# GregsBoard1.net
KiCad netlist of a schematic drawn in EAGLE
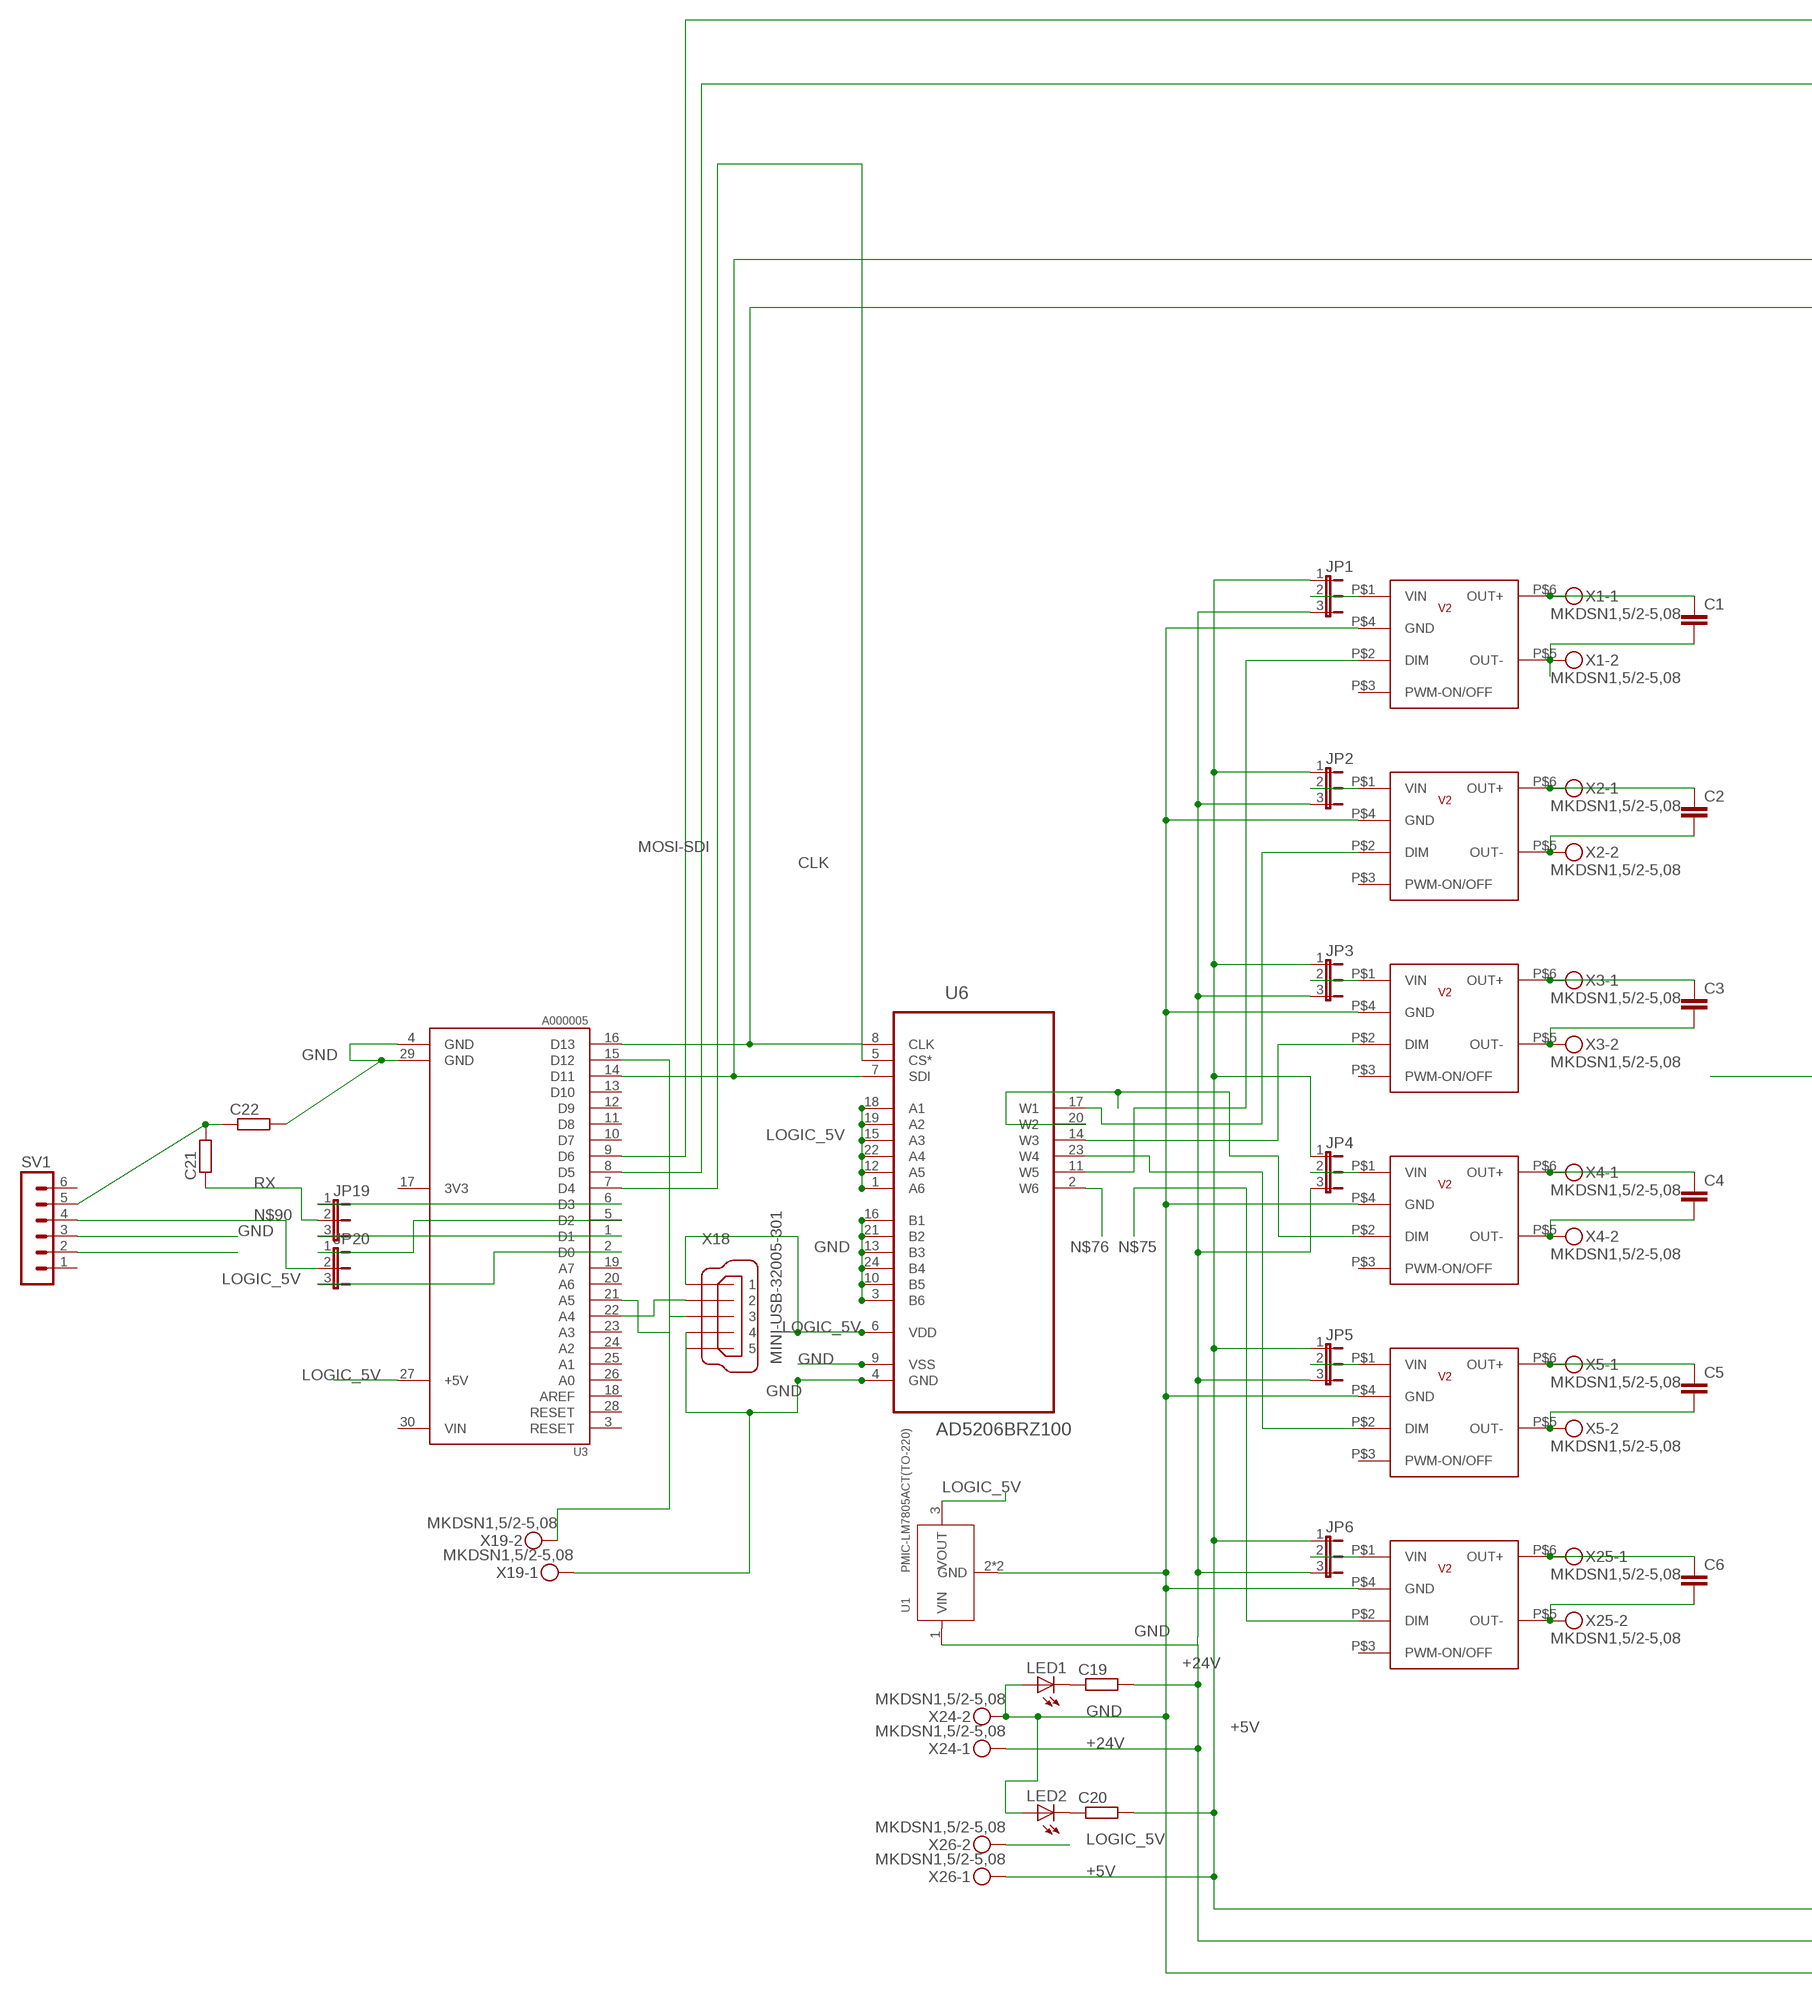
[diagram p0: schematic, sheet 1, part 1 of 2]
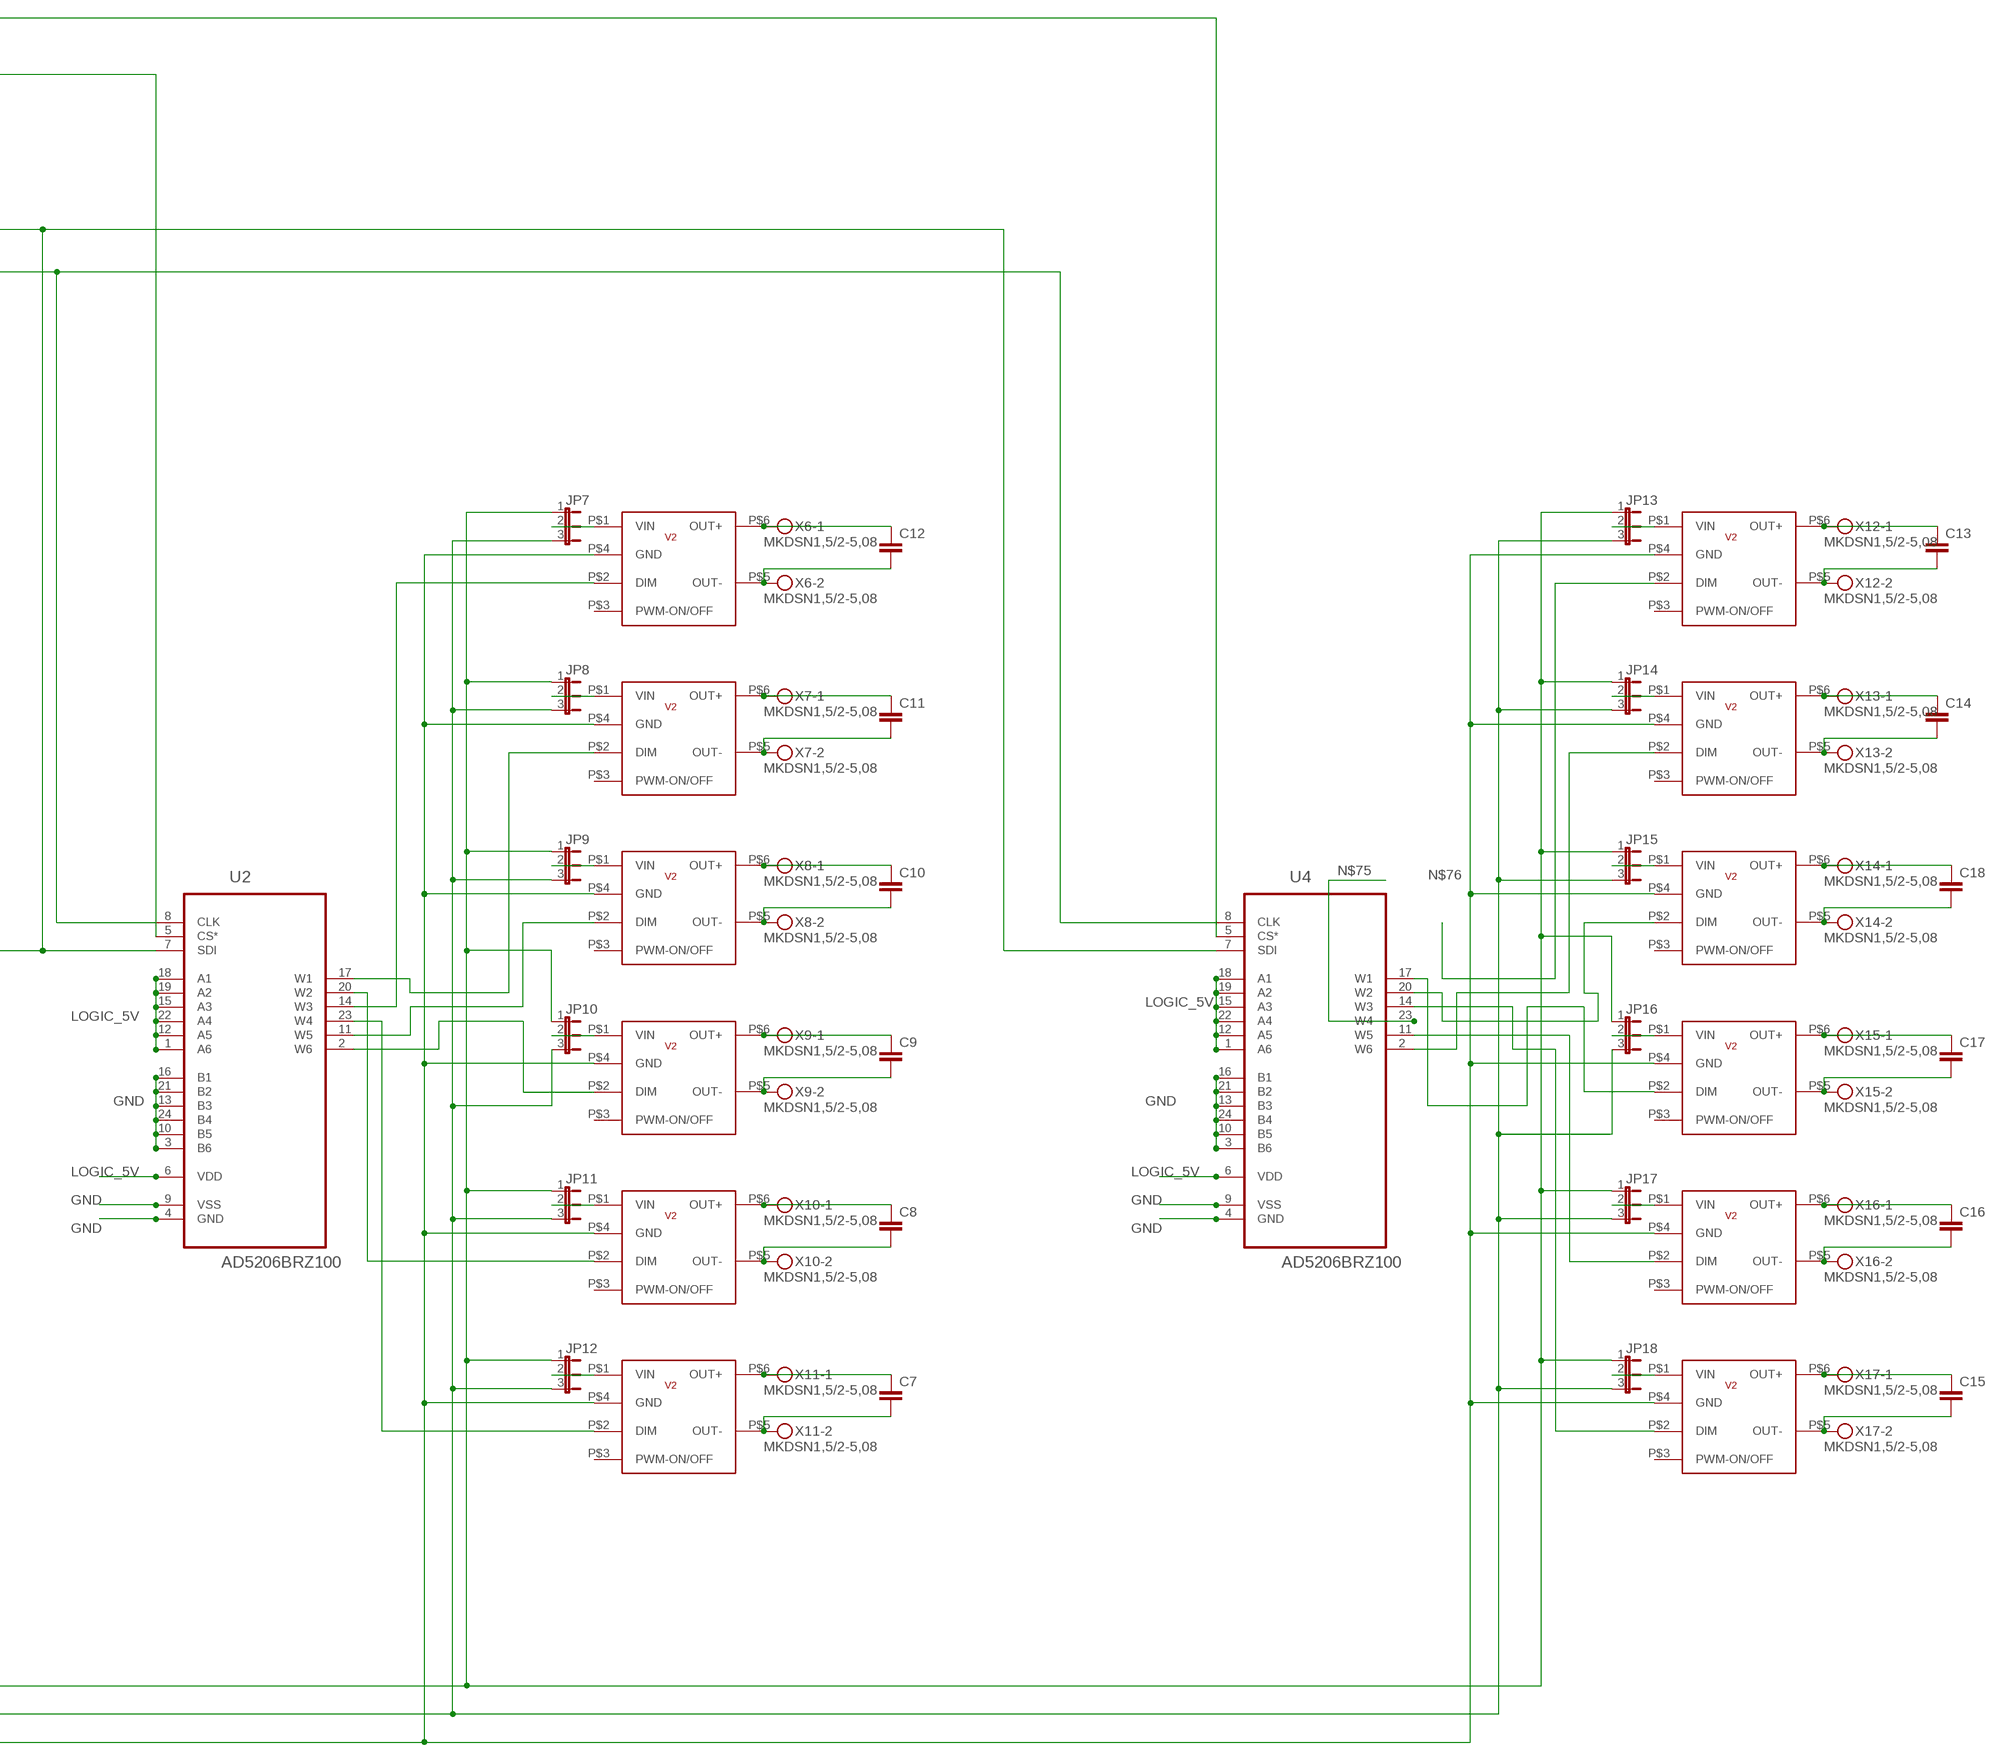
[diagram p1: schematic, sheet 1, part 2 of 2]

(export (version "E")
  (design (tool "Eeschema 10.0.6"))
  (components
    (comp (ref "C1")
      (value "C-EU050-045X075")
      (footprint "eagle-import:C050-045X075")
      (libsource (lib "eagle-import") (part "C-EU050-045X075"))
    )
    (comp (ref "C2")
      (value "C-EU050-045X075")
      (footprint "eagle-import:C050-045X075")
      (libsource (lib "eagle-import") (part "C-EU050-045X075"))
    )
    (comp (ref "C3")
      (value "C-EU050-045X075")
      (footprint "eagle-import:C050-045X075")
      (libsource (lib "eagle-import") (part "C-EU050-045X075"))
    )
    (comp (ref "C4")
      (value "C-EU050-045X075")
      (footprint "eagle-import:C050-045X075")
      (libsource (lib "eagle-import") (part "C-EU050-045X075"))
    )
    (comp (ref "C5")
      (value "C-EU050-045X075")
      (footprint "eagle-import:C050-045X075")
      (libsource (lib "eagle-import") (part "C-EU050-045X075"))
    )
    (comp (ref "C6")
      (value "C-EU050-045X075")
      (footprint "eagle-import:C050-045X075")
      (libsource (lib "eagle-import") (part "C-EU050-045X075"))
    )
    (comp (ref "C7")
      (value "C-EU050-045X075")
      (footprint "eagle-import:C050-045X075")
      (libsource (lib "eagle-import") (part "C-EU050-045X075"))
    )
    (comp (ref "C8")
      (value "C-EU050-045X075")
      (footprint "eagle-import:C050-045X075")
      (libsource (lib "eagle-import") (part "C-EU050-045X075"))
    )
    (comp (ref "C9")
      (value "C-EU050-045X075")
      (footprint "eagle-import:C050-045X075")
      (libsource (lib "eagle-import") (part "C-EU050-045X075"))
    )
    (comp (ref "C10")
      (value "C-EU050-045X075")
      (footprint "eagle-import:C050-045X075")
      (libsource (lib "eagle-import") (part "C-EU050-045X075"))
    )
    (comp (ref "C11")
      (value "C-EU050-045X075")
      (footprint "eagle-import:C050-045X075")
      (libsource (lib "eagle-import") (part "C-EU050-045X075"))
    )
    (comp (ref "C12")
      (value "C-EU050-045X075")
      (footprint "eagle-import:C050-045X075")
      (libsource (lib "eagle-import") (part "C-EU050-045X075"))
    )
    (comp (ref "C13")
      (value "C-EU050-045X075")
      (footprint "eagle-import:C050-045X075")
      (libsource (lib "eagle-import") (part "C-EU050-045X075"))
    )
    (comp (ref "C14")
      (value "C-EU050-045X075")
      (footprint "eagle-import:C050-045X075")
      (libsource (lib "eagle-import") (part "C-EU050-045X075"))
    )
    (comp (ref "C15")
      (value "C-EU050-045X075")
      (footprint "eagle-import:C050-045X075")
      (libsource (lib "eagle-import") (part "C-EU050-045X075"))
    )
    (comp (ref "C16")
      (value "C-EU050-045X075")
      (footprint "eagle-import:C050-045X075")
      (libsource (lib "eagle-import") (part "C-EU050-045X075"))
    )
    (comp (ref "C17")
      (value "C-EU050-045X075")
      (footprint "eagle-import:C050-045X075")
      (libsource (lib "eagle-import") (part "C-EU050-045X075"))
    )
    (comp (ref "C18")
      (value "C-EU050-045X075")
      (footprint "eagle-import:C050-045X075")
      (libsource (lib "eagle-import") (part "C-EU050-045X075"))
    )
    (comp (ref "C19")
      (value "R-EU_0207/7")
      (footprint "eagle-import:0207_7")
      (libsource (lib "eagle-import") (part "R-EU_0207/7"))
    )
    (comp (ref "C20")
      (value "R-EU_0207/7")
      (footprint "eagle-import:0207_7")
      (libsource (lib "eagle-import") (part "R-EU_0207/7"))
    )
    (comp (ref "C21")
      (value "R-EU_0207/7")
      (footprint "eagle-import:0207_7")
      (libsource (lib "eagle-import") (part "R-EU_0207/7"))
    )
    (comp (ref "C22")
      (value "R-EU_0207/7")
      (footprint "eagle-import:0207_7")
      (libsource (lib "eagle-import") (part "R-EU_0207/7"))
    )
    (comp (ref "IC1")
      (value "RCD-24_MY_DEV")
      (footprint "eagle-import:RCD24-DIP")
      (libsource (lib "eagle-import") (part "RCD-24_MY_DEV"))
    )
    (comp (ref "IC2")
      (value "RCD-24_MY_DEV")
      (footprint "eagle-import:RCD24-DIP")
      (libsource (lib "eagle-import") (part "RCD-24_MY_DEV"))
    )
    (comp (ref "IC3")
      (value "RCD-24_MY_DEV")
      (footprint "eagle-import:RCD24-DIP")
      (libsource (lib "eagle-import") (part "RCD-24_MY_DEV"))
    )
    (comp (ref "IC4")
      (value "RCD-24_MY_DEV")
      (footprint "eagle-import:RCD24-DIP")
      (libsource (lib "eagle-import") (part "RCD-24_MY_DEV"))
    )
    (comp (ref "IC5")
      (value "RCD-24_MY_DEV")
      (footprint "eagle-import:RCD24-DIP")
      (libsource (lib "eagle-import") (part "RCD-24_MY_DEV"))
    )
    (comp (ref "IC6")
      (value "RCD-24_MY_DEV")
      (footprint "eagle-import:RCD24-DIP")
      (libsource (lib "eagle-import") (part "RCD-24_MY_DEV"))
    )
    (comp (ref "IC7")
      (value "RCD-24_MY_DEV")
      (footprint "eagle-import:RCD24-DIP")
      (libsource (lib "eagle-import") (part "RCD-24_MY_DEV"))
    )
    (comp (ref "IC8")
      (value "RCD-24_MY_DEV")
      (footprint "eagle-import:RCD24-DIP")
      (libsource (lib "eagle-import") (part "RCD-24_MY_DEV"))
    )
    (comp (ref "IC9")
      (value "RCD-24_MY_DEV")
      (footprint "eagle-import:RCD24-DIP")
      (libsource (lib "eagle-import") (part "RCD-24_MY_DEV"))
    )
    (comp (ref "IC10")
      (value "RCD-24_MY_DEV")
      (footprint "eagle-import:RCD24-DIP")
      (libsource (lib "eagle-import") (part "RCD-24_MY_DEV"))
    )
    (comp (ref "IC11")
      (value "RCD-24_MY_DEV")
      (footprint "eagle-import:RCD24-DIP")
      (libsource (lib "eagle-import") (part "RCD-24_MY_DEV"))
    )
    (comp (ref "IC12")
      (value "RCD-24_MY_DEV")
      (footprint "eagle-import:RCD24-DIP")
      (libsource (lib "eagle-import") (part "RCD-24_MY_DEV"))
    )
    (comp (ref "IC13")
      (value "RCD-24_MY_DEV")
      (footprint "eagle-import:RCD24-DIP")
      (libsource (lib "eagle-import") (part "RCD-24_MY_DEV"))
    )
    (comp (ref "IC14")
      (value "RCD-24_MY_DEV")
      (footprint "eagle-import:RCD24-DIP")
      (libsource (lib "eagle-import") (part "RCD-24_MY_DEV"))
    )
    (comp (ref "IC15")
      (value "RCD-24_MY_DEV")
      (footprint "eagle-import:RCD24-DIP")
      (libsource (lib "eagle-import") (part "RCD-24_MY_DEV"))
    )
    (comp (ref "IC16")
      (value "RCD-24_MY_DEV")
      (footprint "eagle-import:RCD24-DIP")
      (libsource (lib "eagle-import") (part "RCD-24_MY_DEV"))
    )
    (comp (ref "IC17")
      (value "RCD-24_MY_DEV")
      (footprint "eagle-import:RCD24-DIP")
      (libsource (lib "eagle-import") (part "RCD-24_MY_DEV"))
    )
    (comp (ref "IC18")
      (value "RCD-24_MY_DEV")
      (footprint "eagle-import:RCD24-DIP")
      (libsource (lib "eagle-import") (part "RCD-24_MY_DEV"))
    )
    (comp (ref "JP1")
      (value "JP2E")
      (footprint "eagle-import:JP2")
      (libsource (lib "eagle-import") (part "JP2E"))
    )
    (comp (ref "JP2")
      (value "JP2E")
      (footprint "eagle-import:JP2")
      (libsource (lib "eagle-import") (part "JP2E"))
    )
    (comp (ref "JP3")
      (value "JP2E")
      (footprint "eagle-import:JP2")
      (libsource (lib "eagle-import") (part "JP2E"))
    )
    (comp (ref "JP4")
      (value "JP2E")
      (footprint "eagle-import:JP2")
      (libsource (lib "eagle-import") (part "JP2E"))
    )
    (comp (ref "JP5")
      (value "JP2E")
      (footprint "eagle-import:JP2")
      (libsource (lib "eagle-import") (part "JP2E"))
    )
    (comp (ref "JP6")
      (value "JP2E")
      (footprint "eagle-import:JP2")
      (libsource (lib "eagle-import") (part "JP2E"))
    )
    (comp (ref "JP7")
      (value "JP2E")
      (footprint "eagle-import:JP2")
      (libsource (lib "eagle-import") (part "JP2E"))
    )
    (comp (ref "JP8")
      (value "JP2E")
      (footprint "eagle-import:JP2")
      (libsource (lib "eagle-import") (part "JP2E"))
    )
    (comp (ref "JP9")
      (value "JP2E")
      (footprint "eagle-import:JP2")
      (libsource (lib "eagle-import") (part "JP2E"))
    )
    (comp (ref "JP10")
      (value "JP2E")
      (footprint "eagle-import:JP2")
      (libsource (lib "eagle-import") (part "JP2E"))
    )
    (comp (ref "JP11")
      (value "JP2E")
      (footprint "eagle-import:JP2")
      (libsource (lib "eagle-import") (part "JP2E"))
    )
    (comp (ref "JP12")
      (value "JP2E")
      (footprint "eagle-import:JP2")
      (libsource (lib "eagle-import") (part "JP2E"))
    )
    (comp (ref "JP13")
      (value "JP2E")
      (footprint "eagle-import:JP2")
      (libsource (lib "eagle-import") (part "JP2E"))
    )
    (comp (ref "JP14")
      (value "JP2E")
      (footprint "eagle-import:JP2")
      (libsource (lib "eagle-import") (part "JP2E"))
    )
    (comp (ref "JP15")
      (value "JP2E")
      (footprint "eagle-import:JP2")
      (libsource (lib "eagle-import") (part "JP2E"))
    )
    (comp (ref "JP16")
      (value "JP2E")
      (footprint "eagle-import:JP2")
      (libsource (lib "eagle-import") (part "JP2E"))
    )
    (comp (ref "JP17")
      (value "JP2E")
      (footprint "eagle-import:JP2")
      (libsource (lib "eagle-import") (part "JP2E"))
    )
    (comp (ref "JP18")
      (value "JP2E")
      (footprint "eagle-import:JP2")
      (libsource (lib "eagle-import") (part "JP2E"))
    )
    (comp (ref "JP19")
      (value "JP2E")
      (footprint "eagle-import:JP2")
      (libsource (lib "eagle-import") (part "JP2E"))
    )
    (comp (ref "JP20")
      (value "JP2E")
      (footprint "eagle-import:JP2")
      (libsource (lib "eagle-import") (part "JP2E"))
    )
    (comp (ref "LED1")
      (value "LEDB152")
      (footprint "eagle-import:Q62902-B152")
      (libsource (lib "eagle-import") (part "LEDB152"))
    )
    (comp (ref "LED2")
      (value "LEDB152")
      (footprint "eagle-import:Q62902-B152")
      (libsource (lib "eagle-import") (part "LEDB152"))
    )
    (comp (ref "SV1")
      (value "MA06-1")
      (footprint "eagle-import:MA06-1")
      (libsource (lib "eagle-import") (part "MA06-1"))
    )
    (comp (ref "U1")
      (value "PMIC-LM7805ACT(TO-220)")
      (footprint "eagle-import:TO-220")
      (fields (field (name "MF") "ON Semiconductor") (field (name "MP") "LM7805ACT"))
      (libsource (lib "eagle-import") (part "PMIC-LM7805ACT(TO-220)"))
    )
    (comp (ref "U2")
      (value "AD5206BRZ100")
      (footprint "eagle-import:SOIC127P1032X265-24N")
      (fields (field (name "MF") "Analog"))
      (libsource (lib "eagle-import") (part "AD5206BRZ100"))
    )
    (comp (ref "U3")
      (value "A000005")
      (footprint "eagle-import:ARDUINO_A000005")
      (fields (field (name "MF") "Arduino"))
      (libsource (lib "eagle-import") (part "A000005"))
    )
    (comp (ref "U4")
      (value "AD5206BRZ100")
      (footprint "eagle-import:SOIC127P1032X265-24N")
      (fields (field (name "MF") "Analog"))
      (libsource (lib "eagle-import") (part "AD5206BRZ100"))
    )
    (comp (ref "U6")
      (value "AD5206BRZ100")
      (footprint "eagle-import:SOIC127P1032X265-24N")
      (fields (field (name "MF") "Analog"))
      (libsource (lib "eagle-import") (part "AD5206BRZ100"))
    )
    (comp (ref "X1")
      (value "MKDSN1,5/2-5,08")
      (footprint "eagle-import:MKDSN1,5_2-5,08")
      (libsource (lib "eagle-import") (part "MKDSN1,5/2-5,08"))
    )
    (comp (ref "X2")
      (value "MKDSN1,5/2-5,08")
      (footprint "eagle-import:MKDSN1,5_2-5,08")
      (libsource (lib "eagle-import") (part "MKDSN1,5/2-5,08"))
    )
    (comp (ref "X3")
      (value "MKDSN1,5/2-5,08")
      (footprint "eagle-import:MKDSN1,5_2-5,08")
      (libsource (lib "eagle-import") (part "MKDSN1,5/2-5,08"))
    )
    (comp (ref "X4")
      (value "MKDSN1,5/2-5,08")
      (footprint "eagle-import:MKDSN1,5_2-5,08")
      (libsource (lib "eagle-import") (part "MKDSN1,5/2-5,08"))
    )
    (comp (ref "X5")
      (value "MKDSN1,5/2-5,08")
      (footprint "eagle-import:MKDSN1,5_2-5,08")
      (libsource (lib "eagle-import") (part "MKDSN1,5/2-5,08"))
    )
    (comp (ref "X6")
      (value "MKDSN1,5/2-5,08")
      (footprint "eagle-import:MKDSN1,5_2-5,08")
      (libsource (lib "eagle-import") (part "MKDSN1,5/2-5,08"))
    )
    (comp (ref "X7")
      (value "MKDSN1,5/2-5,08")
      (footprint "eagle-import:MKDSN1,5_2-5,08")
      (libsource (lib "eagle-import") (part "MKDSN1,5/2-5,08"))
    )
    (comp (ref "X8")
      (value "MKDSN1,5/2-5,08")
      (footprint "eagle-import:MKDSN1,5_2-5,08")
      (libsource (lib "eagle-import") (part "MKDSN1,5/2-5,08"))
    )
    (comp (ref "X9")
      (value "MKDSN1,5/2-5,08")
      (footprint "eagle-import:MKDSN1,5_2-5,08")
      (libsource (lib "eagle-import") (part "MKDSN1,5/2-5,08"))
    )
    (comp (ref "X10")
      (value "MKDSN1,5/2-5,08")
      (footprint "eagle-import:MKDSN1,5_2-5,08")
      (libsource (lib "eagle-import") (part "MKDSN1,5/2-5,08"))
    )
    (comp (ref "X11")
      (value "MKDSN1,5/2-5,08")
      (footprint "eagle-import:MKDSN1,5_2-5,08")
      (libsource (lib "eagle-import") (part "MKDSN1,5/2-5,08"))
    )
    (comp (ref "X12")
      (value "MKDSN1,5/2-5,08")
      (footprint "eagle-import:MKDSN1,5_2-5,08")
      (libsource (lib "eagle-import") (part "MKDSN1,5/2-5,08"))
    )
    (comp (ref "X13")
      (value "MKDSN1,5/2-5,08")
      (footprint "eagle-import:MKDSN1,5_2-5,08")
      (libsource (lib "eagle-import") (part "MKDSN1,5/2-5,08"))
    )
    (comp (ref "X14")
      (value "MKDSN1,5/2-5,08")
      (footprint "eagle-import:MKDSN1,5_2-5,08")
      (libsource (lib "eagle-import") (part "MKDSN1,5/2-5,08"))
    )
    (comp (ref "X15")
      (value "MKDSN1,5/2-5,08")
      (footprint "eagle-import:MKDSN1,5_2-5,08")
      (libsource (lib "eagle-import") (part "MKDSN1,5/2-5,08"))
    )
    (comp (ref "X16")
      (value "MKDSN1,5/2-5,08")
      (footprint "eagle-import:MKDSN1,5_2-5,08")
      (libsource (lib "eagle-import") (part "MKDSN1,5/2-5,08"))
    )
    (comp (ref "X17")
      (value "MKDSN1,5/2-5,08")
      (footprint "eagle-import:MKDSN1,5_2-5,08")
      (libsource (lib "eagle-import") (part "MKDSN1,5/2-5,08"))
    )
    (comp (ref "X18")
      (value "MINI-USB-32005-301")
      (footprint "eagle-import:32005-301")
      (libsource (lib "eagle-import") (part "MINI-USB-32005-301"))
    )
    (comp (ref "X19")
      (value "MKDSN1,5/2-5,08")
      (footprint "eagle-import:MKDSN1,5_2-5,08")
      (libsource (lib "eagle-import") (part "MKDSN1,5/2-5,08"))
    )
    (comp (ref "X24")
      (value "MKDSN1,5/2-5,08")
      (footprint "eagle-import:MKDSN1,5_2-5,08")
      (libsource (lib "eagle-import") (part "MKDSN1,5/2-5,08"))
    )
    (comp (ref "X25")
      (value "MKDSN1,5/2-5,08")
      (footprint "eagle-import:MKDSN1,5_2-5,08")
      (libsource (lib "eagle-import") (part "MKDSN1,5/2-5,08"))
    )
    (comp (ref "X26")
      (value "MKDSN1,5/2-5,08")
      (footprint "eagle-import:MKDSN1,5_2-5,08")
      (libsource (lib "eagle-import") (part "MKDSN1,5/2-5,08"))
    )
  )
  (nets
    (net (code "1") (name "/+5V") (class "Default")
      (node (ref "C20") (pin "2") (pinfunction "2_2") (pintype "passive"))
      (node (ref "JP1") (pin "1") (pinfunction "1_1") (pintype "passive"))
      (node (ref "JP10") (pin "1") (pinfunction "1_1") (pintype "passive"))
      (node (ref "JP11") (pin "1") (pinfunction "1_1") (pintype "passive"))
      (node (ref "JP12") (pin "1") (pinfunction "1_1") (pintype "passive"))
      (node (ref "JP13") (pin "1") (pinfunction "1_1") (pintype "passive"))
      (node (ref "JP14") (pin "1") (pinfunction "1_1") (pintype "passive"))
      (node (ref "JP15") (pin "1") (pinfunction "1_1") (pintype "passive"))
      (node (ref "JP16") (pin "1") (pinfunction "1_1") (pintype "passive"))
      (node (ref "JP17") (pin "1") (pinfunction "1_1") (pintype "passive"))
      (node (ref "JP18") (pin "1") (pinfunction "1_1") (pintype "passive"))
      (node (ref "JP2") (pin "1") (pinfunction "1_1") (pintype "passive"))
      (node (ref "JP3") (pin "1") (pinfunction "1_1") (pintype "passive"))
      (node (ref "JP4") (pin "1") (pinfunction "1_1") (pintype "passive"))
      (node (ref "JP5") (pin "1") (pinfunction "1_1") (pintype "passive"))
      (node (ref "JP6") (pin "1") (pinfunction "1_1") (pintype "passive"))
      (node (ref "JP7") (pin "1") (pinfunction "1_1") (pintype "passive"))
      (node (ref "JP8") (pin "1") (pinfunction "1_1") (pintype "passive"))
      (node (ref "JP9") (pin "1") (pinfunction "1_1") (pintype "passive"))
      (node (ref "X26") (pin "1") (pinfunction "KL_1") (pintype "passive"))
    )
    (net (code "2") (name "/+24V") (class "Default")
      (node (ref "C19") (pin "2") (pinfunction "2_2") (pintype "passive"))
      (node (ref "JP1") (pin "3") (pinfunction "3_3") (pintype "passive"))
      (node (ref "JP10") (pin "3") (pinfunction "3_3") (pintype "passive"))
      (node (ref "JP11") (pin "3") (pinfunction "3_3") (pintype "passive"))
      (node (ref "JP12") (pin "3") (pinfunction "3_3") (pintype "passive"))
      (node (ref "JP13") (pin "3") (pinfunction "3_3") (pintype "passive"))
      (node (ref "JP14") (pin "3") (pinfunction "3_3") (pintype "passive"))
      (node (ref "JP15") (pin "3") (pinfunction "3_3") (pintype "passive"))
      (node (ref "JP16") (pin "3") (pinfunction "3_3") (pintype "passive"))
      (node (ref "JP17") (pin "3") (pinfunction "3_3") (pintype "passive"))
      (node (ref "JP18") (pin "3") (pinfunction "3_3") (pintype "passive"))
      (node (ref "JP2") (pin "3") (pinfunction "3_3") (pintype "passive"))
      (node (ref "JP3") (pin "3") (pinfunction "3_3") (pintype "passive"))
      (node (ref "JP4") (pin "3") (pinfunction "3_3") (pintype "passive"))
      (node (ref "JP5") (pin "3") (pinfunction "3_3") (pintype "passive"))
      (node (ref "JP6") (pin "3") (pinfunction "3_3") (pintype "passive"))
      (node (ref "JP7") (pin "3") (pinfunction "3_3") (pintype "passive"))
      (node (ref "JP8") (pin "3") (pinfunction "3_3") (pintype "passive"))
      (node (ref "JP9") (pin "3") (pinfunction "3_3") (pintype "passive"))
      (node (ref "U1") (pin "1") (pinfunction "VIN_1") (pintype "bidirectional"))
      (node (ref "X24") (pin "1") (pinfunction "KL_1") (pintype "passive"))
    )
    (net (code "3") (name "/CLK") (class "Default")
      (node (ref "U2") (pin "8") (pinfunction "CLK_8") (pintype "passive"))
      (node (ref "U3") (pin "16") (pinfunction "D13_16") (pintype "bidirectional"))
      (node (ref "U4") (pin "8") (pinfunction "CLK_8") (pintype "passive"))
      (node (ref "U6") (pin "8") (pinfunction "CLK_8") (pintype "passive"))
    )
    (net (code "4") (name "/GND") (class "Default")
      (node (ref "C22") (pin "2") (pinfunction "2_2") (pintype "passive"))
      (node (ref "IC1") (pin "P$4") (pinfunction "GND_P$4") (pintype "bidirectional"))
      (node (ref "IC10") (pin "P$4") (pinfunction "GND_P$4") (pintype "bidirectional"))
      (node (ref "IC11") (pin "P$4") (pinfunction "GND_P$4") (pintype "bidirectional"))
      (node (ref "IC12") (pin "P$4") (pinfunction "GND_P$4") (pintype "bidirectional"))
      (node (ref "IC13") (pin "P$4") (pinfunction "GND_P$4") (pintype "bidirectional"))
      (node (ref "IC14") (pin "P$4") (pinfunction "GND_P$4") (pintype "bidirectional"))
      (node (ref "IC15") (pin "P$4") (pinfunction "GND_P$4") (pintype "bidirectional"))
      (node (ref "IC16") (pin "P$4") (pinfunction "GND_P$4") (pintype "bidirectional"))
      (node (ref "IC17") (pin "P$4") (pinfunction "GND_P$4") (pintype "bidirectional"))
      (node (ref "IC18") (pin "P$4") (pinfunction "GND_P$4") (pintype "bidirectional"))
      (node (ref "IC2") (pin "P$4") (pinfunction "GND_P$4") (pintype "bidirectional"))
      (node (ref "IC3") (pin "P$4") (pinfunction "GND_P$4") (pintype "bidirectional"))
      (node (ref "IC4") (pin "P$4") (pinfunction "GND_P$4") (pintype "bidirectional"))
      (node (ref "IC5") (pin "P$4") (pinfunction "GND_P$4") (pintype "bidirectional"))
      (node (ref "IC6") (pin "P$4") (pinfunction "GND_P$4") (pintype "bidirectional"))
      (node (ref "IC7") (pin "P$4") (pinfunction "GND_P$4") (pintype "bidirectional"))
      (node (ref "IC8") (pin "P$4") (pinfunction "GND_P$4") (pintype "bidirectional"))
      (node (ref "IC9") (pin "P$4") (pinfunction "GND_P$4") (pintype "bidirectional"))
      (node (ref "LED1") (pin "A") (pinfunction "A_A") (pintype "passive"))
      (node (ref "LED2") (pin "A") (pinfunction "A_A") (pintype "passive"))
      (node (ref "SV1") (pin "3") (pinfunction "3_3") (pintype "passive"))
      (node (ref "U1") (pin "2") (pinfunction "GND_2") (pintype "bidirectional"))
      (node (ref "U1") (pin "HEAT") (pinfunction "GND_HEAT") (pintype "bidirectional"))
      (node (ref "U2") (pin "10") (pinfunction "B5_10") (pintype "passive"))
      (node (ref "U2") (pin "13") (pinfunction "B3_13") (pintype "passive"))
      (node (ref "U2") (pin "16") (pinfunction "B1_16") (pintype "passive"))
      (node (ref "U2") (pin "21") (pinfunction "B2_21") (pintype "passive"))
      (node (ref "U2") (pin "24") (pinfunction "B4_24") (pintype "passive"))
      (node (ref "U2") (pin "3") (pinfunction "B6_3") (pintype "passive"))
      (node (ref "U2") (pin "4") (pinfunction "GND_4") (pintype "passive"))
      (node (ref "U2") (pin "9") (pinfunction "VSS_9") (pintype "power_in"))
      (node (ref "U3") (pin "29") (pinfunction "GND_29") (pintype "power_in"))
      (node (ref "U3") (pin "4") (pinfunction "GND_4") (pintype "power_in"))
      (node (ref "U4") (pin "10") (pinfunction "B5_10") (pintype "passive"))
      (node (ref "U4") (pin "13") (pinfunction "B3_13") (pintype "passive"))
      (node (ref "U4") (pin "16") (pinfunction "B1_16") (pintype "passive"))
      (node (ref "U4") (pin "21") (pinfunction "B2_21") (pintype "passive"))
      (node (ref "U4") (pin "24") (pinfunction "B4_24") (pintype "passive"))
      (node (ref "U4") (pin "3") (pinfunction "B6_3") (pintype "passive"))
      (node (ref "U4") (pin "4") (pinfunction "GND_4") (pintype "passive"))
      (node (ref "U4") (pin "9") (pinfunction "VSS_9") (pintype "power_in"))
      (node (ref "U6") (pin "10") (pinfunction "B5_10") (pintype "passive"))
      (node (ref "U6") (pin "13") (pinfunction "B3_13") (pintype "passive"))
      (node (ref "U6") (pin "16") (pinfunction "B1_16") (pintype "passive"))
      (node (ref "U6") (pin "21") (pinfunction "B2_21") (pintype "passive"))
      (node (ref "U6") (pin "24") (pinfunction "B4_24") (pintype "passive"))
      (node (ref "U6") (pin "3") (pinfunction "B6_3") (pintype "passive"))
      (node (ref "U6") (pin "4") (pinfunction "GND_4") (pintype "passive"))
      (node (ref "U6") (pin "9") (pinfunction "VSS_9") (pintype "power_in"))
      (node (ref "X18") (pin "4") (pinfunction "4_4") (pintype "passive"))
      (node (ref "X19") (pin "1") (pinfunction "KL_1") (pintype "passive"))
      (node (ref "X24") (pin "2") (pinfunction "KL_2") (pintype "passive"))
    )
    (net (code "5") (name "/LOGIC_5V") (class "Default")
      (node (ref "SV1") (pin "2") (pinfunction "2_2") (pintype "passive"))
      (node (ref "U1") (pin "3") (pinfunction "VOUT_3") (pintype "bidirectional"))
      (node (ref "U2") (pin "1") (pinfunction "A6_1") (pintype "passive"))
      (node (ref "U2") (pin "12") (pinfunction "A5_12") (pintype "passive"))
      (node (ref "U2") (pin "15") (pinfunction "A3_15") (pintype "passive"))
      (node (ref "U2") (pin "18") (pinfunction "A1_18") (pintype "passive"))
      (node (ref "U2") (pin "19") (pinfunction "A2_19") (pintype "passive"))
      (node (ref "U2") (pin "22") (pinfunction "A4_22") (pintype "passive"))
      (node (ref "U2") (pin "6") (pinfunction "VDD_6") (pintype "power_in"))
      (node (ref "U3") (pin "27") (pinfunction "+5V_27") (pintype "power_in"))
      (node (ref "U4") (pin "1") (pinfunction "A6_1") (pintype "passive"))
      (node (ref "U4") (pin "12") (pinfunction "A5_12") (pintype "passive"))
      (node (ref "U4") (pin "15") (pinfunction "A3_15") (pintype "passive"))
      (node (ref "U4") (pin "18") (pinfunction "A1_18") (pintype "passive"))
      (node (ref "U4") (pin "19") (pinfunction "A2_19") (pintype "passive"))
      (node (ref "U4") (pin "22") (pinfunction "A4_22") (pintype "passive"))
      (node (ref "U4") (pin "6") (pinfunction "VDD_6") (pintype "power_in"))
      (node (ref "U6") (pin "1") (pinfunction "A6_1") (pintype "passive"))
      (node (ref "U6") (pin "12") (pinfunction "A5_12") (pintype "passive"))
      (node (ref "U6") (pin "15") (pinfunction "A3_15") (pintype "passive"))
      (node (ref "U6") (pin "18") (pinfunction "A1_18") (pintype "passive"))
      (node (ref "U6") (pin "19") (pinfunction "A2_19") (pintype "passive"))
      (node (ref "U6") (pin "22") (pinfunction "A4_22") (pintype "passive"))
      (node (ref "U6") (pin "6") (pinfunction "VDD_6") (pintype "power_in"))
      (node (ref "X18") (pin "1") (pinfunction "1_1") (pintype "passive"))
      (node (ref "X26") (pin "2") (pinfunction "KL_2") (pintype "passive"))
    )
    (net (code "6") (name "/MOSI-SDI") (class "Default")
      (node (ref "U2") (pin "7") (pinfunction "SDI_7") (pintype "passive"))
      (node (ref "U3") (pin "14") (pinfunction "D11_14") (pintype "bidirectional"))
      (node (ref "U4") (pin "7") (pinfunction "SDI_7") (pintype "passive"))
      (node (ref "U6") (pin "7") (pinfunction "SDI_7") (pintype "passive"))
    )
    (net (code "7") (name "/N$75") (class "Default")
      (node (ref "IC1") (pin "P$2") (pinfunction "DIM_P$2") (pintype "bidirectional"))
      (node (ref "U4") (pin "23") (pinfunction "W4_23") (pintype "passive"))
    )
    (net (code "8") (name "/N$76") (class "Default")
      (node (ref "IC13") (pin "P$2") (pinfunction "DIM_P$2") (pintype "bidirectional"))
      (node (ref "U6") (pin "2") (pinfunction "W6_2") (pintype "passive"))
    )
    (net (code "9") (name "/N$90") (class "Default")
      (node (ref "JP20") (pin "2") (pinfunction "2_2") (pintype "passive"))
      (node (ref "SV1") (pin "4") (pinfunction "4_4") (pintype "passive"))
    )
    (net (code "10") (name "/RX") (class "Default")
      (node (ref "C21") (pin "2") (pinfunction "2_2") (pintype "passive"))
      (node (ref "C22") (pin "1") (pinfunction "1_1") (pintype "passive"))
      (node (ref "SV1") (pin "5") (pinfunction "5_5") (pintype "passive"))
    )
    (net (code "11") (name "/VIN") (class "Default")
      (node (ref "U3") (pin "30") (pinfunction "VIN_30") (pintype "power_in"))
    )
    (net (code "12") (name "Net-(C21-Pad1)") (class "Default")
      (node (ref "C21") (pin "1") (pinfunction "1_1") (pintype "passive"))
      (node (ref "JP19") (pin "2") (pinfunction "2_2") (pintype "passive"))
    )
    (net (code "13") (name "Net-(IC1-OUT+)") (class "Default")
      (node (ref "C6") (pin "1") (pinfunction "1_1") (pintype "passive"))
      (node (ref "IC1") (pin "P$6") (pinfunction "OUT+_P$6") (pintype "bidirectional"))
      (node (ref "X25") (pin "1") (pinfunction "KL_1") (pintype "passive"))
    )
    (net (code "14") (name "Net-(IC1-OUT-)") (class "Default")
      (node (ref "C6") (pin "2") (pinfunction "2_2") (pintype "passive"))
      (node (ref "IC1") (pin "P$5") (pinfunction "OUT-_P$5") (pintype "bidirectional"))
      (node (ref "X25") (pin "2") (pinfunction "KL_2") (pintype "passive"))
    )
    (net (code "15") (name "Net-(IC1-VIN)") (class "Default")
      (node (ref "IC1") (pin "P$1") (pinfunction "VIN_P$1") (pintype "bidirectional"))
      (node (ref "JP6") (pin "2") (pinfunction "2_2") (pintype "passive"))
    )
    (net (code "16") (name "Net-(IC2-DIM)") (class "Default")
      (node (ref "IC2") (pin "P$2") (pinfunction "DIM_P$2") (pintype "bidirectional"))
      (node (ref "U6") (pin "11") (pinfunction "W5_11") (pintype "passive"))
    )
    (net (code "17") (name "Net-(IC2-OUT+)") (class "Default")
      (node (ref "C1") (pin "1") (pinfunction "1_1") (pintype "passive"))
      (node (ref "IC2") (pin "P$6") (pinfunction "OUT+_P$6") (pintype "bidirectional"))
      (node (ref "X1") (pin "1") (pinfunction "KL_1") (pintype "passive"))
    )
    (net (code "18") (name "Net-(IC2-OUT-)") (class "Default")
      (node (ref "C1") (pin "2") (pinfunction "2_2") (pintype "passive"))
      (node (ref "IC2") (pin "P$5") (pinfunction "OUT-_P$5") (pintype "bidirectional"))
      (node (ref "X1") (pin "2") (pinfunction "KL_2") (pintype "passive"))
    )
    (net (code "19") (name "Net-(IC2-VIN)") (class "Default")
      (node (ref "IC2") (pin "P$1") (pinfunction "VIN_P$1") (pintype "bidirectional"))
      (node (ref "JP1") (pin "2") (pinfunction "2_2") (pintype "passive"))
    )
    (net (code "20") (name "Net-(IC3-DIM)") (class "Default")
      (node (ref "IC3") (pin "P$2") (pinfunction "DIM_P$2") (pintype "bidirectional"))
      (node (ref "U6") (pin "17") (pinfunction "W1_17") (pintype "passive"))
    )
    (net (code "21") (name "Net-(IC3-OUT+)") (class "Default")
      (node (ref "C2") (pin "1") (pinfunction "1_1") (pintype "passive"))
      (node (ref "IC3") (pin "P$6") (pinfunction "OUT+_P$6") (pintype "bidirectional"))
      (node (ref "X2") (pin "1") (pinfunction "KL_1") (pintype "passive"))
    )
    (net (code "22") (name "Net-(IC3-OUT-)") (class "Default")
      (node (ref "C2") (pin "2") (pinfunction "2_2") (pintype "passive"))
      (node (ref "IC3") (pin "P$5") (pinfunction "OUT-_P$5") (pintype "bidirectional"))
      (node (ref "X2") (pin "2") (pinfunction "KL_2") (pintype "passive"))
    )
    (net (code "23") (name "Net-(IC3-VIN)") (class "Default")
      (node (ref "IC3") (pin "P$1") (pinfunction "VIN_P$1") (pintype "bidirectional"))
      (node (ref "JP2") (pin "2") (pinfunction "2_2") (pintype "passive"))
    )
    (net (code "24") (name "Net-(IC4-DIM)") (class "Default")
      (node (ref "IC4") (pin "P$2") (pinfunction "DIM_P$2") (pintype "bidirectional"))
      (node (ref "U6") (pin "14") (pinfunction "W3_14") (pintype "passive"))
    )
    (net (code "25") (name "Net-(IC4-OUT+)") (class "Default")
      (node (ref "C3") (pin "1") (pinfunction "1_1") (pintype "passive"))
      (node (ref "IC4") (pin "P$6") (pinfunction "OUT+_P$6") (pintype "bidirectional"))
      (node (ref "X3") (pin "1") (pinfunction "KL_1") (pintype "passive"))
    )
    (net (code "26") (name "Net-(IC4-OUT-)") (class "Default")
      (node (ref "C3") (pin "2") (pinfunction "2_2") (pintype "passive"))
      (node (ref "IC4") (pin "P$5") (pinfunction "OUT-_P$5") (pintype "bidirectional"))
      (node (ref "X3") (pin "2") (pinfunction "KL_2") (pintype "passive"))
    )
    (net (code "27") (name "Net-(IC4-VIN)") (class "Default")
      (node (ref "IC4") (pin "P$1") (pinfunction "VIN_P$1") (pintype "bidirectional"))
      (node (ref "JP3") (pin "2") (pinfunction "2_2") (pintype "passive"))
    )
    (net (code "28") (name "Net-(IC5-DIM)") (class "Default")
      (node (ref "IC5") (pin "P$2") (pinfunction "DIM_P$2") (pintype "bidirectional"))
      (node (ref "U6") (pin "20") (pinfunction "W2_20") (pintype "passive"))
    )
    (net (code "29") (name "Net-(IC5-OUT+)") (class "Default")
      (node (ref "C4") (pin "1") (pinfunction "1_1") (pintype "passive"))
      (node (ref "IC5") (pin "P$6") (pinfunction "OUT+_P$6") (pintype "bidirectional"))
      (node (ref "X4") (pin "1") (pinfunction "KL_1") (pintype "passive"))
    )
    (net (code "30") (name "Net-(IC5-OUT-)") (class "Default")
      (node (ref "C4") (pin "2") (pinfunction "2_2") (pintype "passive"))
      (node (ref "IC5") (pin "P$5") (pinfunction "OUT-_P$5") (pintype "bidirectional"))
      (node (ref "X4") (pin "2") (pinfunction "KL_2") (pintype "passive"))
    )
    (net (code "31") (name "Net-(IC5-VIN)") (class "Default")
      (node (ref "IC5") (pin "P$1") (pinfunction "VIN_P$1") (pintype "bidirectional"))
      (node (ref "JP4") (pin "2") (pinfunction "2_2") (pintype "passive"))
    )
    (net (code "32") (name "Net-(IC6-DIM)") (class "Default")
      (node (ref "IC6") (pin "P$2") (pinfunction "DIM_P$2") (pintype "bidirectional"))
      (node (ref "U6") (pin "23") (pinfunction "W4_23") (pintype "passive"))
    )
    (net (code "33") (name "Net-(IC6-OUT+)") (class "Default")
      (node (ref "C5") (pin "1") (pinfunction "1_1") (pintype "passive"))
      (node (ref "IC6") (pin "P$6") (pinfunction "OUT+_P$6") (pintype "bidirectional"))
      (node (ref "X5") (pin "1") (pinfunction "KL_1") (pintype "passive"))
    )
    (net (code "34") (name "Net-(IC6-OUT-)") (class "Default")
      (node (ref "C5") (pin "2") (pinfunction "2_2") (pintype "passive"))
      (node (ref "IC6") (pin "P$5") (pinfunction "OUT-_P$5") (pintype "bidirectional"))
      (node (ref "X5") (pin "2") (pinfunction "KL_2") (pintype "passive"))
    )
    (net (code "35") (name "Net-(IC6-VIN)") (class "Default")
      (node (ref "IC6") (pin "P$1") (pinfunction "VIN_P$1") (pintype "bidirectional"))
      (node (ref "JP5") (pin "2") (pinfunction "2_2") (pintype "passive"))
    )
    (net (code "36") (name "Net-(IC7-DIM)") (class "Default")
      (node (ref "IC7") (pin "P$2") (pinfunction "DIM_P$2") (pintype "bidirectional"))
      (node (ref "U2") (pin "14") (pinfunction "W3_14") (pintype "passive"))
    )
    (net (code "37") (name "Net-(IC7-OUT+)") (class "Default")
      (node (ref "C12") (pin "1") (pinfunction "1_1") (pintype "passive"))
      (node (ref "IC7") (pin "P$6") (pinfunction "OUT+_P$6") (pintype "bidirectional"))
      (node (ref "X6") (pin "1") (pinfunction "KL_1") (pintype "passive"))
    )
    (net (code "38") (name "Net-(IC7-OUT-)") (class "Default")
      (node (ref "C12") (pin "2") (pinfunction "2_2") (pintype "passive"))
      (node (ref "IC7") (pin "P$5") (pinfunction "OUT-_P$5") (pintype "bidirectional"))
      (node (ref "X6") (pin "2") (pinfunction "KL_2") (pintype "passive"))
    )
    (net (code "39") (name "Net-(IC7-VIN)") (class "Default")
      (node (ref "IC7") (pin "P$1") (pinfunction "VIN_P$1") (pintype "bidirectional"))
      (node (ref "JP7") (pin "2") (pinfunction "2_2") (pintype "passive"))
    )
    (net (code "40") (name "Net-(IC8-DIM)") (class "Default")
      (node (ref "IC8") (pin "P$2") (pinfunction "DIM_P$2") (pintype "bidirectional"))
      (node (ref "U2") (pin "17") (pinfunction "W1_17") (pintype "passive"))
    )
    (net (code "41") (name "Net-(IC8-OUT+)") (class "Default")
      (node (ref "C11") (pin "1") (pinfunction "1_1") (pintype "passive"))
      (node (ref "IC8") (pin "P$6") (pinfunction "OUT+_P$6") (pintype "bidirectional"))
      (node (ref "X7") (pin "1") (pinfunction "KL_1") (pintype "passive"))
    )
    (net (code "42") (name "Net-(IC8-OUT-)") (class "Default")
      (node (ref "C11") (pin "2") (pinfunction "2_2") (pintype "passive"))
      (node (ref "IC8") (pin "P$5") (pinfunction "OUT-_P$5") (pintype "bidirectional"))
      (node (ref "X7") (pin "2") (pinfunction "KL_2") (pintype "passive"))
    )
    (net (code "43") (name "Net-(IC8-VIN)") (class "Default")
      (node (ref "IC8") (pin "P$1") (pinfunction "VIN_P$1") (pintype "bidirectional"))
      (node (ref "JP8") (pin "2") (pinfunction "2_2") (pintype "passive"))
    )
    (net (code "44") (name "Net-(IC9-DIM)") (class "Default")
      (node (ref "IC9") (pin "P$2") (pinfunction "DIM_P$2") (pintype "bidirectional"))
      (node (ref "U2") (pin "11") (pinfunction "W5_11") (pintype "passive"))
    )
    (net (code "45") (name "Net-(IC9-OUT+)") (class "Default")
      (node (ref "C10") (pin "1") (pinfunction "1_1") (pintype "passive"))
      (node (ref "IC9") (pin "P$6") (pinfunction "OUT+_P$6") (pintype "bidirectional"))
      (node (ref "X8") (pin "1") (pinfunction "KL_1") (pintype "passive"))
    )
    (net (code "46") (name "Net-(IC9-OUT-)") (class "Default")
      (node (ref "C10") (pin "2") (pinfunction "2_2") (pintype "passive"))
      (node (ref "IC9") (pin "P$5") (pinfunction "OUT-_P$5") (pintype "bidirectional"))
      (node (ref "X8") (pin "2") (pinfunction "KL_2") (pintype "passive"))
    )
    (net (code "47") (name "Net-(IC9-VIN)") (class "Default")
      (node (ref "IC9") (pin "P$1") (pinfunction "VIN_P$1") (pintype "bidirectional"))
      (node (ref "JP9") (pin "2") (pinfunction "2_2") (pintype "passive"))
    )
    (net (code "48") (name "Net-(IC10-DIM)") (class "Default")
      (node (ref "IC10") (pin "P$2") (pinfunction "DIM_P$2") (pintype "bidirectional"))
      (node (ref "U2") (pin "2") (pinfunction "W6_2") (pintype "passive"))
    )
    (net (code "49") (name "Net-(IC10-OUT+)") (class "Default")
      (node (ref "C9") (pin "1") (pinfunction "1_1") (pintype "passive"))
      (node (ref "IC10") (pin "P$6") (pinfunction "OUT+_P$6") (pintype "bidirectional"))
      (node (ref "X9") (pin "1") (pinfunction "KL_1") (pintype "passive"))
    )
    (net (code "50") (name "Net-(IC10-OUT-)") (class "Default")
      (node (ref "C9") (pin "2") (pinfunction "2_2") (pintype "passive"))
      (node (ref "IC10") (pin "P$5") (pinfunction "OUT-_P$5") (pintype "bidirectional"))
      (node (ref "X9") (pin "2") (pinfunction "KL_2") (pintype "passive"))
    )
    (net (code "51") (name "Net-(IC10-VIN)") (class "Default")
      (node (ref "IC10") (pin "P$1") (pinfunction "VIN_P$1") (pintype "bidirectional"))
      (node (ref "JP10") (pin "2") (pinfunction "2_2") (pintype "passive"))
    )
    (net (code "52") (name "Net-(IC11-DIM)") (class "Default")
      (node (ref "IC11") (pin "P$2") (pinfunction "DIM_P$2") (pintype "bidirectional"))
      (node (ref "U2") (pin "20") (pinfunction "W2_20") (pintype "passive"))
    )
    (net (code "53") (name "Net-(IC11-OUT+)") (class "Default")
      (node (ref "C8") (pin "1") (pinfunction "1_1") (pintype "passive"))
      (node (ref "IC11") (pin "P$6") (pinfunction "OUT+_P$6") (pintype "bidirectional"))
      (node (ref "X10") (pin "1") (pinfunction "KL_1") (pintype "passive"))
    )
    (net (code "54") (name "Net-(IC11-OUT-)") (class "Default")
      (node (ref "C8") (pin "2") (pinfunction "2_2") (pintype "passive"))
      (node (ref "IC11") (pin "P$5") (pinfunction "OUT-_P$5") (pintype "bidirectional"))
      (node (ref "X10") (pin "2") (pinfunction "KL_2") (pintype "passive"))
    )
    (net (code "55") (name "Net-(IC11-VIN)") (class "Default")
      (node (ref "IC11") (pin "P$1") (pinfunction "VIN_P$1") (pintype "bidirectional"))
      (node (ref "JP11") (pin "2") (pinfunction "2_2") (pintype "passive"))
    )
    (net (code "56") (name "Net-(IC12-DIM)") (class "Default")
      (node (ref "IC12") (pin "P$2") (pinfunction "DIM_P$2") (pintype "bidirectional"))
      (node (ref "U2") (pin "23") (pinfunction "W4_23") (pintype "passive"))
    )
    (net (code "57") (name "Net-(IC12-OUT+)") (class "Default")
      (node (ref "C7") (pin "1") (pinfunction "1_1") (pintype "passive"))
      (node (ref "IC12") (pin "P$6") (pinfunction "OUT+_P$6") (pintype "bidirectional"))
      (node (ref "X11") (pin "1") (pinfunction "KL_1") (pintype "passive"))
    )
    (net (code "58") (name "Net-(IC12-OUT-)") (class "Default")
      (node (ref "C7") (pin "2") (pinfunction "2_2") (pintype "passive"))
      (node (ref "IC12") (pin "P$5") (pinfunction "OUT-_P$5") (pintype "bidirectional"))
      (node (ref "X11") (pin "2") (pinfunction "KL_2") (pintype "passive"))
    )
    (net (code "59") (name "Net-(IC12-VIN)") (class "Default")
      (node (ref "IC12") (pin "P$1") (pinfunction "VIN_P$1") (pintype "bidirectional"))
      (node (ref "JP12") (pin "2") (pinfunction "2_2") (pintype "passive"))
    )
    (net (code "60") (name "Net-(IC13-OUT+)") (class "Default")
      (node (ref "C13") (pin "1") (pinfunction "1_1") (pintype "passive"))
      (node (ref "IC13") (pin "P$6") (pinfunction "OUT+_P$6") (pintype "bidirectional"))
      (node (ref "X12") (pin "1") (pinfunction "KL_1") (pintype "passive"))
    )
    (net (code "61") (name "Net-(IC13-OUT-)") (class "Default")
      (node (ref "C13") (pin "2") (pinfunction "2_2") (pintype "passive"))
      (node (ref "IC13") (pin "P$5") (pinfunction "OUT-_P$5") (pintype "bidirectional"))
      (node (ref "X12") (pin "2") (pinfunction "KL_2") (pintype "passive"))
    )
    (net (code "62") (name "Net-(IC13-VIN)") (class "Default")
      (node (ref "IC13") (pin "P$1") (pinfunction "VIN_P$1") (pintype "bidirectional"))
      (node (ref "JP13") (pin "2") (pinfunction "2_2") (pintype "passive"))
    )
    (net (code "63") (name "Net-(IC14-DIM)") (class "Default")
      (node (ref "IC14") (pin "P$2") (pinfunction "DIM_P$2") (pintype "bidirectional"))
      (node (ref "U4") (pin "2") (pinfunction "W6_2") (pintype "passive"))
    )
    (net (code "64") (name "Net-(IC14-OUT+)") (class "Default")
      (node (ref "C14") (pin "1") (pinfunction "1_1") (pintype "passive"))
      (node (ref "IC14") (pin "P$6") (pinfunction "OUT+_P$6") (pintype "bidirectional"))
      (node (ref "X13") (pin "1") (pinfunction "KL_1") (pintype "passive"))
    )
    (net (code "65") (name "Net-(IC14-OUT-)") (class "Default")
      (node (ref "C14") (pin "2") (pinfunction "2_2") (pintype "passive"))
      (node (ref "IC14") (pin "P$5") (pinfunction "OUT-_P$5") (pintype "bidirectional"))
      (node (ref "X13") (pin "2") (pinfunction "KL_2") (pintype "passive"))
    )
    (net (code "66") (name "Net-(IC14-VIN)") (class "Default")
      (node (ref "IC14") (pin "P$1") (pinfunction "VIN_P$1") (pintype "bidirectional"))
      (node (ref "JP14") (pin "2") (pinfunction "2_2") (pintype "passive"))
    )
    (net (code "67") (name "Net-(IC15-DIM)") (class "Default")
      (node (ref "IC15") (pin "P$2") (pinfunction "DIM_P$2") (pintype "bidirectional"))
      (node (ref "U4") (pin "20") (pinfunction "W2_20") (pintype "passive"))
    )
    (net (code "68") (name "Net-(IC15-OUT+)") (class "Default")
      (node (ref "C18") (pin "1") (pinfunction "1_1") (pintype "passive"))
      (node (ref "IC15") (pin "P$6") (pinfunction "OUT+_P$6") (pintype "bidirectional"))
      (node (ref "X14") (pin "1") (pinfunction "KL_1") (pintype "passive"))
    )
    (net (code "69") (name "Net-(IC15-OUT-)") (class "Default")
      (node (ref "C18") (pin "2") (pinfunction "2_2") (pintype "passive"))
      (node (ref "IC15") (pin "P$5") (pinfunction "OUT-_P$5") (pintype "bidirectional"))
      (node (ref "X14") (pin "2") (pinfunction "KL_2") (pintype "passive"))
    )
    (net (code "70") (name "Net-(IC15-VIN)") (class "Default")
      (node (ref "IC15") (pin "P$1") (pinfunction "VIN_P$1") (pintype "bidirectional"))
      (node (ref "JP15") (pin "2") (pinfunction "2_2") (pintype "passive"))
    )
    (net (code "71") (name "Net-(IC16-DIM)") (class "Default")
      (node (ref "IC16") (pin "P$2") (pinfunction "DIM_P$2") (pintype "bidirectional"))
      (node (ref "U4") (pin "17") (pinfunction "W1_17") (pintype "passive"))
    )
    (net (code "72") (name "Net-(IC16-OUT+)") (class "Default")
      (node (ref "C17") (pin "1") (pinfunction "1_1") (pintype "passive"))
      (node (ref "IC16") (pin "P$6") (pinfunction "OUT+_P$6") (pintype "bidirectional"))
      (node (ref "X15") (pin "1") (pinfunction "KL_1") (pintype "passive"))
    )
    (net (code "73") (name "Net-(IC16-OUT-)") (class "Default")
      (node (ref "C17") (pin "2") (pinfunction "2_2") (pintype "passive"))
      (node (ref "IC16") (pin "P$5") (pinfunction "OUT-_P$5") (pintype "bidirectional"))
      (node (ref "X15") (pin "2") (pinfunction "KL_2") (pintype "passive"))
    )
    (net (code "74") (name "Net-(IC16-VIN)") (class "Default")
      (node (ref "IC16") (pin "P$1") (pinfunction "VIN_P$1") (pintype "bidirectional"))
      (node (ref "JP16") (pin "2") (pinfunction "2_2") (pintype "passive"))
    )
    (net (code "75") (name "Net-(IC17-DIM)") (class "Default")
      (node (ref "IC17") (pin "P$2") (pinfunction "DIM_P$2") (pintype "bidirectional"))
      (node (ref "U4") (pin "11") (pinfunction "W5_11") (pintype "passive"))
    )
    (net (code "76") (name "Net-(IC17-OUT+)") (class "Default")
      (node (ref "C16") (pin "1") (pinfunction "1_1") (pintype "passive"))
      (node (ref "IC17") (pin "P$6") (pinfunction "OUT+_P$6") (pintype "bidirectional"))
      (node (ref "X16") (pin "1") (pinfunction "KL_1") (pintype "passive"))
    )
    (net (code "77") (name "Net-(IC17-OUT-)") (class "Default")
      (node (ref "C16") (pin "2") (pinfunction "2_2") (pintype "passive"))
      (node (ref "IC17") (pin "P$5") (pinfunction "OUT-_P$5") (pintype "bidirectional"))
      (node (ref "X16") (pin "2") (pinfunction "KL_2") (pintype "passive"))
    )
    (net (code "78") (name "Net-(IC17-VIN)") (class "Default")
      (node (ref "IC17") (pin "P$1") (pinfunction "VIN_P$1") (pintype "bidirectional"))
      (node (ref "JP17") (pin "2") (pinfunction "2_2") (pintype "passive"))
    )
    (net (code "79") (name "Net-(IC18-DIM)") (class "Default")
      (node (ref "IC18") (pin "P$2") (pinfunction "DIM_P$2") (pintype "bidirectional"))
      (node (ref "U4") (pin "14") (pinfunction "W3_14") (pintype "passive"))
    )
    (net (code "80") (name "Net-(IC18-OUT+)") (class "Default")
      (node (ref "C15") (pin "1") (pinfunction "1_1") (pintype "passive"))
      (node (ref "IC18") (pin "P$6") (pinfunction "OUT+_P$6") (pintype "bidirectional"))
      (node (ref "X17") (pin "1") (pinfunction "KL_1") (pintype "passive"))
    )
    (net (code "81") (name "Net-(IC18-OUT-)") (class "Default")
      (node (ref "C15") (pin "2") (pinfunction "2_2") (pintype "passive"))
      (node (ref "IC18") (pin "P$5") (pinfunction "OUT-_P$5") (pintype "bidirectional"))
      (node (ref "X17") (pin "2") (pinfunction "KL_2") (pintype "passive"))
    )
    (net (code "82") (name "Net-(IC18-VIN)") (class "Default")
      (node (ref "IC18") (pin "P$1") (pinfunction "VIN_P$1") (pintype "bidirectional"))
      (node (ref "JP18") (pin "2") (pinfunction "2_2") (pintype "passive"))
    )
    (net (code "83") (name "Net-(LED1-C)") (class "Default")
      (node (ref "C19") (pin "1") (pinfunction "1_1") (pintype "passive"))
      (node (ref "LED1") (pin "K") (pinfunction "C_K") (pintype "passive"))
    )
    (net (code "84") (name "Net-(LED2-C)") (class "Default")
      (node (ref "C20") (pin "1") (pinfunction "1_1") (pintype "passive"))
      (node (ref "LED2") (pin "K") (pinfunction "C_K") (pintype "passive"))
    )
    (net (code "85") (name "Net-(U2-CS*)") (class "Default")
      (node (ref "U2") (pin "5") (pinfunction "CS*_5") (pintype "passive"))
      (node (ref "U3") (pin "8") (pinfunction "D5_8") (pintype "bidirectional"))
    )
    (net (code "86") (name "Net-(U3-A4)") (class "Default")
      (node (ref "U3") (pin "22") (pinfunction "A4_22") (pintype "input"))
      (node (ref "X18") (pin "2") (pinfunction "2_2") (pintype "passive"))
    )
    (net (code "87") (name "Net-(U3-A5)") (class "Default")
      (node (ref "U3") (pin "21") (pinfunction "A5_21") (pintype "input"))
      (node (ref "X18") (pin "3") (pinfunction "3_3") (pintype "passive"))
    )
    (net (code "88") (name "Net-(U3-D0)") (class "Default")
      (node (ref "JP20") (pin "3") (pinfunction "3_3") (pintype "passive"))
      (node (ref "U3") (pin "2") (pinfunction "D0_2") (pintype "bidirectional"))
    )
    (net (code "89") (name "Net-(U3-D1)") (class "Default")
      (node (ref "JP19") (pin "3") (pinfunction "3_3") (pintype "passive"))
      (node (ref "U3") (pin "1") (pinfunction "D1_1") (pintype "bidirectional"))
    )
    (net (code "90") (name "Net-(U3-D2)") (class "Default")
      (node (ref "JP20") (pin "1") (pinfunction "1_1") (pintype "passive"))
      (node (ref "U3") (pin "5") (pinfunction "D2_5") (pintype "bidirectional"))
    )
    (net (code "91") (name "Net-(U3-D3)") (class "Default")
      (node (ref "JP19") (pin "1") (pinfunction "1_1") (pintype "passive"))
      (node (ref "U3") (pin "6") (pinfunction "D3_6") (pintype "bidirectional"))
    )
    (net (code "92") (name "Net-(U3-D4)") (class "Default")
      (node (ref "U3") (pin "7") (pinfunction "D4_7") (pintype "bidirectional"))
      (node (ref "U6") (pin "5") (pinfunction "CS*_5") (pintype "passive"))
    )
    (net (code "93") (name "Net-(U3-D6)") (class "Default")
      (node (ref "U3") (pin "9") (pinfunction "D6_9") (pintype "bidirectional"))
      (node (ref "U4") (pin "5") (pinfunction "CS*_5") (pintype "passive"))
    )
    (net (code "94") (name "Net-(U3-D12)") (class "Default")
      (node (ref "U3") (pin "15") (pinfunction "D12_15") (pintype "bidirectional"))
      (node (ref "X19") (pin "2") (pinfunction "KL_2") (pintype "passive"))
    )
    (net (code "95") (name "unconnected-(IC1-PWM-ON{slash}OFF-PadP$3)") (class "Default")
      (node (ref "IC1") (pin "P$3") (pinfunction "PWM-ON/OFF_P$3") (pintype "bidirectional"))
    )
    (net (code "96") (name "unconnected-(IC2-PWM-ON{slash}OFF-PadP$3)") (class "Default")
      (node (ref "IC2") (pin "P$3") (pinfunction "PWM-ON/OFF_P$3") (pintype "bidirectional"))
    )
    (net (code "97") (name "unconnected-(IC3-PWM-ON{slash}OFF-PadP$3)") (class "Default")
      (node (ref "IC3") (pin "P$3") (pinfunction "PWM-ON/OFF_P$3") (pintype "bidirectional"))
    )
    (net (code "98") (name "unconnected-(IC4-PWM-ON{slash}OFF-PadP$3)") (class "Default")
      (node (ref "IC4") (pin "P$3") (pinfunction "PWM-ON/OFF_P$3") (pintype "bidirectional"))
    )
    (net (code "99") (name "unconnected-(IC5-PWM-ON{slash}OFF-PadP$3)") (class "Default")
      (node (ref "IC5") (pin "P$3") (pinfunction "PWM-ON/OFF_P$3") (pintype "bidirectional"))
    )
    (net (code "100") (name "unconnected-(IC6-PWM-ON{slash}OFF-PadP$3)") (class "Default")
      (node (ref "IC6") (pin "P$3") (pinfunction "PWM-ON/OFF_P$3") (pintype "bidirectional"))
    )
    (net (code "101") (name "unconnected-(IC7-PWM-ON{slash}OFF-PadP$3)") (class "Default")
      (node (ref "IC7") (pin "P$3") (pinfunction "PWM-ON/OFF_P$3") (pintype "bidirectional"))
    )
    (net (code "102") (name "unconnected-(IC8-PWM-ON{slash}OFF-PadP$3)") (class "Default")
      (node (ref "IC8") (pin "P$3") (pinfunction "PWM-ON/OFF_P$3") (pintype "bidirectional"))
    )
    (net (code "103") (name "unconnected-(IC9-PWM-ON{slash}OFF-PadP$3)") (class "Default")
      (node (ref "IC9") (pin "P$3") (pinfunction "PWM-ON/OFF_P$3") (pintype "bidirectional"))
    )
    (net (code "104") (name "unconnected-(IC10-PWM-ON{slash}OFF-PadP$3)") (class "Default")
      (node (ref "IC10") (pin "P$3") (pinfunction "PWM-ON/OFF_P$3") (pintype "bidirectional"))
    )
    (net (code "105") (name "unconnected-(IC11-PWM-ON{slash}OFF-PadP$3)") (class "Default")
      (node (ref "IC11") (pin "P$3") (pinfunction "PWM-ON/OFF_P$3") (pintype "bidirectional"))
    )
    (net (code "106") (name "unconnected-(IC12-PWM-ON{slash}OFF-PadP$3)") (class "Default")
      (node (ref "IC12") (pin "P$3") (pinfunction "PWM-ON/OFF_P$3") (pintype "bidirectional"))
    )
    (net (code "107") (name "unconnected-(IC13-PWM-ON{slash}OFF-PadP$3)") (class "Default")
      (node (ref "IC13") (pin "P$3") (pinfunction "PWM-ON/OFF_P$3") (pintype "bidirectional"))
    )
    (net (code "108") (name "unconnected-(IC14-PWM-ON{slash}OFF-PadP$3)") (class "Default")
      (node (ref "IC14") (pin "P$3") (pinfunction "PWM-ON/OFF_P$3") (pintype "bidirectional"))
    )
    (net (code "109") (name "unconnected-(IC15-PWM-ON{slash}OFF-PadP$3)") (class "Default")
      (node (ref "IC15") (pin "P$3") (pinfunction "PWM-ON/OFF_P$3") (pintype "bidirectional"))
    )
    (net (code "110") (name "unconnected-(IC16-PWM-ON{slash}OFF-PadP$3)") (class "Default")
      (node (ref "IC16") (pin "P$3") (pinfunction "PWM-ON/OFF_P$3") (pintype "bidirectional"))
    )
    (net (code "111") (name "unconnected-(IC17-PWM-ON{slash}OFF-PadP$3)") (class "Default")
      (node (ref "IC17") (pin "P$3") (pinfunction "PWM-ON/OFF_P$3") (pintype "bidirectional"))
    )
    (net (code "112") (name "unconnected-(IC18-PWM-ON{slash}OFF-PadP$3)") (class "Default")
      (node (ref "IC18") (pin "P$3") (pinfunction "PWM-ON/OFF_P$3") (pintype "bidirectional"))
    )
    (net (code "113") (name "unconnected-(SV1-Pad1)") (class "Default")
      (node (ref "SV1") (pin "1") (pinfunction "1_1") (pintype "passive"))
    )
    (net (code "114") (name "unconnected-(SV1-Pad6)") (class "Default")
      (node (ref "SV1") (pin "6") (pinfunction "6_6") (pintype "passive"))
    )
    (net (code "115") (name "unconnected-(U3-3V3-Pad17)") (class "Default")
      (node (ref "U3") (pin "17") (pinfunction "3V3_17") (pintype "output"))
    )
    (net (code "116") (name "unconnected-(U3-A0-Pad26)") (class "Default")
      (node (ref "U3") (pin "26") (pinfunction "A0_26") (pintype "input"))
    )
    (net (code "117") (name "unconnected-(U3-A1-Pad25)") (class "Default")
      (node (ref "U3") (pin "25") (pinfunction "A1_25") (pintype "input"))
    )
    (net (code "118") (name "unconnected-(U3-A2-Pad24)") (class "Default")
      (node (ref "U3") (pin "24") (pinfunction "A2_24") (pintype "input"))
    )
    (net (code "119") (name "unconnected-(U3-A3-Pad23)") (class "Default")
      (node (ref "U3") (pin "23") (pinfunction "A3_23") (pintype "input"))
    )
    (net (code "120") (name "unconnected-(U3-A6-Pad20)") (class "Default")
      (node (ref "U3") (pin "20") (pinfunction "A6_20") (pintype "input"))
    )
    (net (code "121") (name "unconnected-(U3-A7-Pad19)") (class "Default")
      (node (ref "U3") (pin "19") (pinfunction "A7_19") (pintype "input"))
    )
    (net (code "122") (name "unconnected-(U3-AREF-Pad18)") (class "Default")
      (node (ref "U3") (pin "18") (pinfunction "AREF_18") (pintype "input"))
    )
    (net (code "123") (name "unconnected-(U3-D7-Pad10)") (class "Default")
      (node (ref "U3") (pin "10") (pinfunction "D7_10") (pintype "bidirectional"))
    )
    (net (code "124") (name "unconnected-(U3-D8-Pad11)") (class "Default")
      (node (ref "U3") (pin "11") (pinfunction "D8_11") (pintype "bidirectional"))
    )
    (net (code "125") (name "unconnected-(U3-D9-Pad12)") (class "Default")
      (node (ref "U3") (pin "12") (pinfunction "D9_12") (pintype "bidirectional"))
    )
    (net (code "126") (name "unconnected-(U3-D10-Pad13)") (class "Default")
      (node (ref "U3") (pin "13") (pinfunction "D10_13") (pintype "bidirectional"))
    )
    (net (code "127") (name "unconnected-(U3-RESET-Pad3)") (class "Default")
      (node (ref "U3") (pin "3") (pinfunction "RESET_3") (pintype "input"))
    )
    (net (code "128") (name "unconnected-(U3-RESET-Pad28)") (class "Default")
      (node (ref "U3") (pin "28") (pinfunction "RESET_28") (pintype "input"))
    )
    (net (code "129") (name "unconnected-(X18-Pad5)") (class "Default")
      (node (ref "X18") (pin "5") (pinfunction "5_5") (pintype "passive"))
    )
  )
)
